# ufo.net
KiCad netlist of a schematic drawn in EAGLE
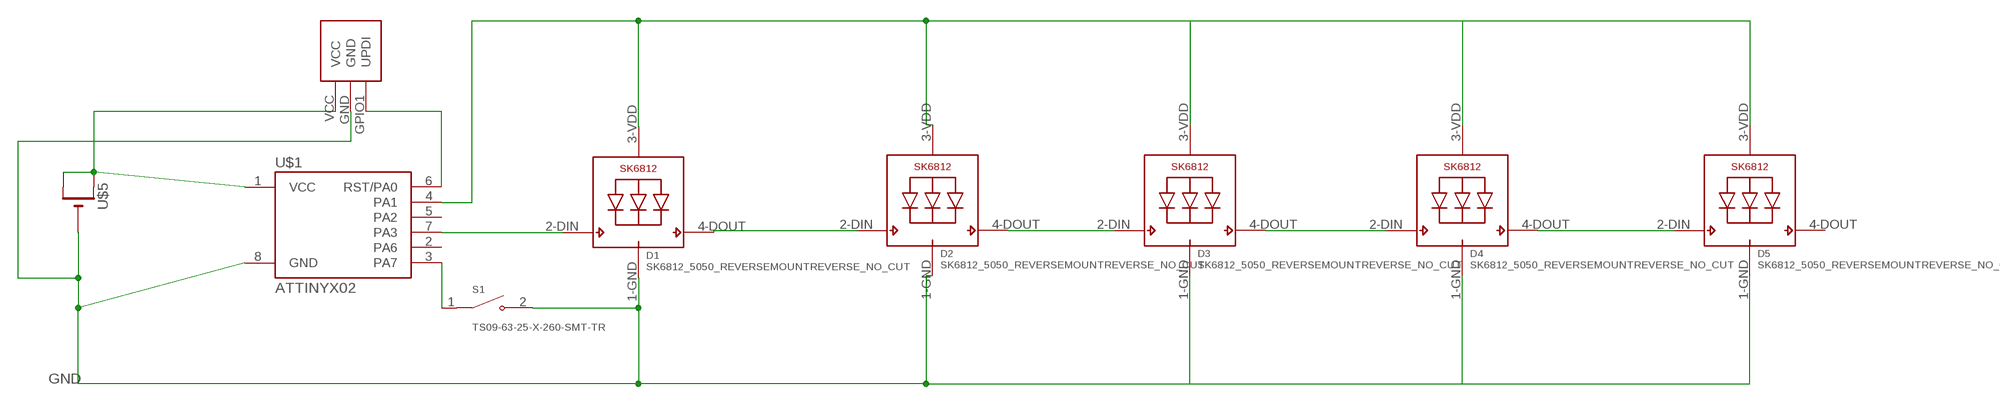
[diagram p0: schematic, sheet 1]

(export (version "E")
  (design (tool "Eeschema 10.0.6"))
  (components
    (comp (ref "D1")
      (value "SK6812_5050_REVERSEMOUNTREVERSE_NO_CUT")
      (footprint "eagle-import:SK6812_REVERSE_NO_CUT")
      (libsource (lib "eagle-import") (part "SK6812_5050_REVERSEMOUNTREVERSE_NO_CUT"))
    )
    (comp (ref "D2")
      (value "SK6812_5050_REVERSEMOUNTREVERSE_NO_CUT")
      (footprint "eagle-import:SK6812_REVERSE_NO_CUT")
      (libsource (lib "eagle-import") (part "SK6812_5050_REVERSEMOUNTREVERSE_NO_CUT"))
    )
    (comp (ref "D3")
      (value "SK6812_5050_REVERSEMOUNTREVERSE_NO_CUT")
      (footprint "eagle-import:SK6812_REVERSE_NO_CUT")
      (libsource (lib "eagle-import") (part "SK6812_5050_REVERSEMOUNTREVERSE_NO_CUT"))
    )
    (comp (ref "D4")
      (value "SK6812_5050_REVERSEMOUNTREVERSE_NO_CUT")
      (footprint "eagle-import:SK6812_REVERSE_NO_CUT")
      (libsource (lib "eagle-import") (part "SK6812_5050_REVERSEMOUNTREVERSE_NO_CUT"))
    )
    (comp (ref "D5")
      (value "SK6812_5050_REVERSEMOUNTREVERSE_NO_CUT")
      (footprint "eagle-import:SK6812_REVERSE_NO_CUT")
      (libsource (lib "eagle-import") (part "SK6812_5050_REVERSEMOUNTREVERSE_NO_CUT"))
    )
    (comp (ref "S1")
      (value "TS09-63-25-X-260-SMT-TR")
      (footprint "eagle-import:SW_TS09-63-25-X-260-SMT-TR")
      (fields (field (name "MANUFACTURER") "CUI Devices"))
      (libsource (lib "eagle-import") (part "TS09-63-25-X-260-SMT-TR"))
    )
    (comp (ref "U$1")
      (value "ATTINYX02")
      (footprint "eagle-import:SOIC08_JEDEC_150MIL")
      (libsource (lib "eagle-import") (part "ATTINYX02"))
    )
    (comp (ref "U$2")
      (value "SAO")
      (footprint "eagle-import:SAO_SMD")
      (libsource (lib "eagle-import") (part "SAO"))
    )
    (comp (ref "U$5")
      (value "CR2032SMT")
      (footprint "eagle-import:CR2032-SMD")
      (libsource (lib "eagle-import") (part "CR2032SMT"))
    )
  )
  (nets
    (net (code "1") (name "/GND") (class "Default")
      (node (ref "D1") (pin "1-GND") (pinfunction "GND_1-GND") (pintype "power_in"))
      (node (ref "D2") (pin "1-GND") (pinfunction "GND_1-GND") (pintype "power_in"))
      (node (ref "D3") (pin "1-GND") (pinfunction "GND_1-GND") (pintype "power_in"))
      (node (ref "D4") (pin "1-GND") (pinfunction "GND_1-GND") (pintype "power_in"))
      (node (ref "D5") (pin "1-GND") (pinfunction "GND_1-GND") (pintype "power_in"))
      (node (ref "S1") (pin "2") (pinfunction "2_2") (pintype "passive"))
      (node (ref "U$1") (pin "8") (pinfunction "GND_8") (pintype "power_in"))
      (node (ref "U$2") (pin "GND") (pinfunction "GND_GND") (pintype "bidirectional"))
      (node (ref "U$5") (pin "-") (pinfunction "-_-") (pintype "passive"))
    )
    (net (code "2") (name "Net-(D1-DI)") (class "Default")
      (node (ref "D1") (pin "2-DIN") (pinfunction "DI_2-DIN") (pintype "input"))
      (node (ref "U$1") (pin "7") (pinfunction "PA3_7") (pintype "bidirectional"))
    )
    (net (code "3") (name "Net-(D1-DO)") (class "Default")
      (node (ref "D1") (pin "4-DOUT") (pinfunction "DO_4-DOUT") (pintype "output"))
      (node (ref "D2") (pin "2-DIN") (pinfunction "DI_2-DIN") (pintype "input"))
    )
    (net (code "4") (name "Net-(D1-VDD)") (class "Default")
      (node (ref "D1") (pin "3-VDD") (pinfunction "VDD_3-VDD") (pintype "power_in"))
      (node (ref "D2") (pin "3-VDD") (pinfunction "VDD_3-VDD") (pintype "power_in"))
      (node (ref "D3") (pin "3-VDD") (pinfunction "VDD_3-VDD") (pintype "power_in"))
      (node (ref "D4") (pin "3-VDD") (pinfunction "VDD_3-VDD") (pintype "power_in"))
      (node (ref "D5") (pin "3-VDD") (pinfunction "VDD_3-VDD") (pintype "power_in"))
      (node (ref "U$1") (pin "4") (pinfunction "PA1_4") (pintype "bidirectional"))
    )
    (net (code "5") (name "Net-(D2-DO)") (class "Default")
      (node (ref "D2") (pin "4-DOUT") (pinfunction "DO_4-DOUT") (pintype "output"))
      (node (ref "D3") (pin "2-DIN") (pinfunction "DI_2-DIN") (pintype "input"))
    )
    (net (code "6") (name "Net-(D3-DO)") (class "Default")
      (node (ref "D3") (pin "4-DOUT") (pinfunction "DO_4-DOUT") (pintype "output"))
      (node (ref "D4") (pin "2-DIN") (pinfunction "DI_2-DIN") (pintype "input"))
    )
    (net (code "7") (name "Net-(D4-DO)") (class "Default")
      (node (ref "D4") (pin "4-DOUT") (pinfunction "DO_4-DOUT") (pintype "output"))
      (node (ref "D5") (pin "2-DIN") (pinfunction "DI_2-DIN") (pintype "input"))
    )
    (net (code "8") (name "Net-(U$1-PA7)") (class "Default")
      (node (ref "S1") (pin "1") (pinfunction "1_1") (pintype "passive"))
      (node (ref "U$1") (pin "3") (pinfunction "PA7_3") (pintype "bidirectional"))
    )
    (net (code "9") (name "Net-(U$1-RST{slash}PA0)") (class "Default")
      (node (ref "U$1") (pin "6") (pinfunction "RST/PA0_6") (pintype "bidirectional"))
      (node (ref "U$2") (pin "GPIO1") (pinfunction "UPDI_GPIO1") (pintype "bidirectional"))
    )
    (net (code "10") (name "Net-(U$1-VCC)") (class "Default")
      (node (ref "U$1") (pin "1") (pinfunction "VCC_1") (pintype "power_in"))
      (node (ref "U$2") (pin "VCC") (pinfunction "VCC_VCC") (pintype "bidirectional"))
      (node (ref "U$5") (pin "+$1") (pinfunction "+_+$1") (pintype "passive"))
      (node (ref "U$5") (pin "+$2") (pinfunction "+1_+$2") (pintype "passive"))
    )
    (net (code "11") (name "unconnected-(D5-DO-Pad4-DOUT)") (class "Default")
      (node (ref "D5") (pin "4-DOUT") (pinfunction "DO_4-DOUT") (pintype "output"))
    )
    (net (code "12") (name "unconnected-(U$1-PA2-Pad5)") (class "Default")
      (node (ref "U$1") (pin "5") (pinfunction "PA2_5") (pintype "bidirectional"))
    )
    (net (code "13") (name "unconnected-(U$1-PA6-Pad2)") (class "Default")
      (node (ref "U$1") (pin "2") (pinfunction "PA6_2") (pintype "bidirectional"))
    )
  )
)
